# MotherBoard.net
KiCad netlist of a schematic drawn in Altium Designer
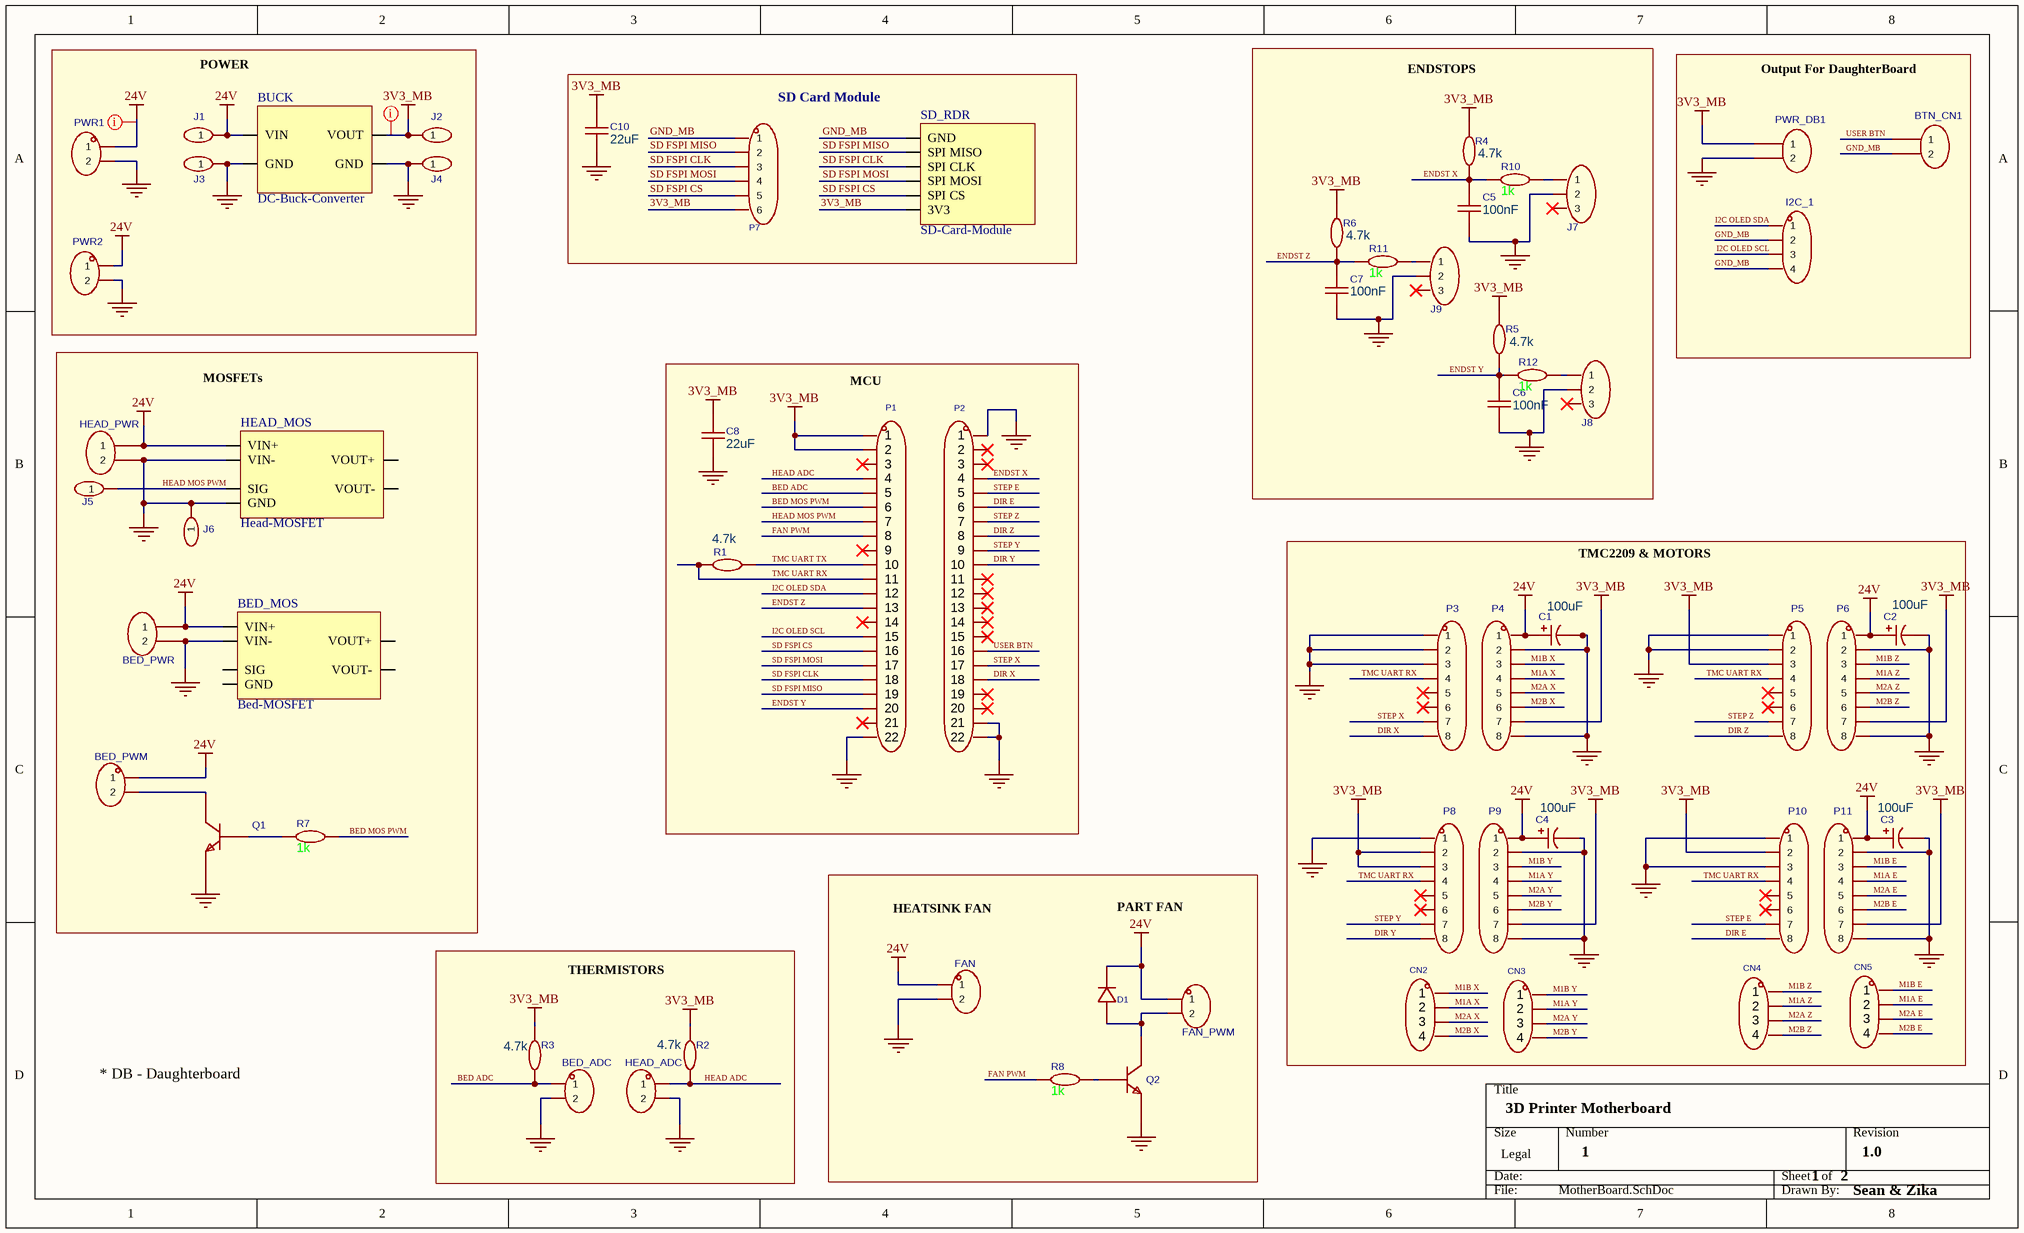
[diagram p0: MotherBoard.SchDoc]

(export (version "E")
  (design (tool "Eeschema 10.0.6"))
  (components
    (comp (ref "BED_ADC")
      (value "sh-xh2.54-2p")
      (footprint "XH-2P")
      (fields (field (name "MANUFACTURER") "深海电子") (field (name "MANUFACTURERPART") "SH-XH2.54-2P"))
      (libsource (lib "FinalProjectSchLib") (part "XH-2P"))
    )
    (comp (ref "BED_MOS")
      (value "Bed-MOSFET")
      (footprint "Bed-MOSFET")
      (libsource (lib "FinalProjectSchLib") (part "Bed-MOSFET"))
    )
    (comp (ref "BED_PWM")
      (value "sh-xh2.54-2p")
      (footprint "XH-2P")
      (fields (field (name "MANUFACTURER") "深海电子") (field (name "MANUFACTURERPART") "SH-XH2.54-2P"))
      (libsource (lib "FinalProjectSchLib") (part "XH-2P"))
    )
    (comp (ref "BED_PWR")
      (value "wj127-5.0-02p-14-00a")
      (footprint "Screw-Terminal-2P")
      (fields
        (field (name "MANUFACTURER") "KANGNEX(康奈克斯电气)")
        (field (name "MANUFACTURERPART") "WJ127-5.0-02P-14-00A")
      )
      (libsource (lib "FinalProjectSchLib") (part "Screw-Terminal-2P"))
    )
    (comp (ref "BTN_CN1")
      (value "wj127-5.0-02p-14-00a")
      (footprint "Screw-Terminal-2P")
      (fields
        (field (name "MANUFACTURER") "KANGNEX(康奈克斯电气)")
        (field (name "MANUFACTURERPART") "WJ127-5.0-02P-14-00A")
      )
      (libsource (lib "FinalProjectSchLib") (part "Screw-Terminal-2P"))
    )
    (comp (ref "BUCK")
      (value "DC-Buck-Converter")
      (footprint "DC-Buck-Converter")
      (libsource (lib "FinalProjectSchLib") (part "DC-Buck-Converter"))
    )
    (comp (ref "C1")
      (value "100uF")
      (footprint "Capacitor-100uF")
      (fields
        (field (name "MANUFACTURER") "DMBJ(振宝佳)")
        (field (name "MANUFACTURERPART") "RVT1H101M0810 100UF 50V")
        (field (name "TOLERANCE") "±20%")
      )
      (libsource (lib "FinalProjectSchLib") (part "Capacitor-100uF"))
    )
    (comp (ref "C2")
      (value "100uF")
      (footprint "Capacitor-100uF")
      (fields
        (field (name "MANUFACTURER") "DMBJ(振宝佳)")
        (field (name "MANUFACTURERPART") "RVT1H101M0810 100UF 50V")
        (field (name "TOLERANCE") "±20%")
      )
      (libsource (lib "FinalProjectSchLib") (part "Capacitor-100uF"))
    )
    (comp (ref "C3")
      (value "100uF")
      (footprint "Capacitor-100uF")
      (fields
        (field (name "MANUFACTURER") "DMBJ(振宝佳)")
        (field (name "MANUFACTURERPART") "RVT1H101M0810 100UF 50V")
        (field (name "TOLERANCE") "±20%")
      )
      (libsource (lib "FinalProjectSchLib") (part "Capacitor-100uF"))
    )
    (comp (ref "C4")
      (value "100uF")
      (footprint "Capacitor-100uF")
      (fields
        (field (name "MANUFACTURER") "DMBJ(振宝佳)")
        (field (name "MANUFACTURERPART") "RVT1H101M0810 100UF 50V")
        (field (name "TOLERANCE") "±20%")
      )
      (libsource (lib "FinalProjectSchLib") (part "Capacitor-100uF"))
    )
    (comp (ref "C5")
      (value "100nF")
      (footprint "Capacitor-100nF-0805")
      (description "Capacitance:100nF Tolerance:±10% Tolerance:±10% Voltage Rating:50V Temperature Coefficient:X7R")
      (fields (field (name "MANUFACTURER") "SAMSUNG(三星)") (field (name "MANUFACTURERPART") "CL21B104KBCNNNC"))
      (libsource (lib "FinalProjectSchLib") (part "Capacitor-100nF-0805"))
    )
    (comp (ref "C6")
      (value "100nF")
      (footprint "Capacitor-100nF-0805")
      (description "Capacitance:100nF Tolerance:±10% Tolerance:±10% Voltage Rating:50V Temperature Coefficient:X7R")
      (fields (field (name "MANUFACTURER") "SAMSUNG(三星)") (field (name "MANUFACTURERPART") "CL21B104KBCNNNC"))
      (libsource (lib "FinalProjectSchLib") (part "Capacitor-100nF-0805"))
    )
    (comp (ref "C7")
      (value "100nF")
      (footprint "Capacitor-100nF-0805")
      (description "Capacitance:100nF Tolerance:±10% Tolerance:±10% Voltage Rating:50V Temperature Coefficient:X7R")
      (fields (field (name "MANUFACTURER") "SAMSUNG(三星)") (field (name "MANUFACTURERPART") "CL21B104KBCNNNC"))
      (libsource (lib "FinalProjectSchLib") (part "Capacitor-100nF-0805"))
    )
    (comp (ref "C8")
      (value "22uF")
      (footprint "Capacitor-22uF-0805")
      (description "Capacitance:22uF Tolerance:±20% Tolerance:±20% Voltage Rating:10V Temperature Coefficient:X5R")
      (fields (field (name "MANUFACTURER") "SAMSUNG(三星)") (field (name "MANUFACTURERPART") "CL21A226MPQNNNE"))
      (libsource (lib "FinalProjectSchLib") (part "Capacitor-22uF-0805"))
    )
    (comp (ref "C10")
      (value "22uF")
      (footprint "Capacitor-22uF-0805")
      (description "Capacitance:22uF Tolerance:±20% Tolerance:±20% Voltage Rating:10V Temperature Coefficient:X5R")
      (fields (field (name "MANUFACTURER") "SAMSUNG(三星)") (field (name "MANUFACTURERPART") "CL21A226MPQNNNE"))
      (libsource (lib "FinalProjectSchLib") (part "Capacitor-22uF-0805"))
    )
    (comp (ref "CN2")
      (value "sh-xh2.54-4p")
      (footprint "XH-4P")
      (fields (field (name "MANUFACTURER") "深海电子") (field (name "MANUFACTURERPART") "SH-XH2.54-4P"))
      (libsource (lib "FinalProjectSchLib") (part "XH-4P"))
    )
    (comp (ref "CN3")
      (value "sh-xh2.54-4p")
      (footprint "XH-4P")
      (fields (field (name "MANUFACTURER") "深海电子") (field (name "MANUFACTURERPART") "SH-XH2.54-4P"))
      (libsource (lib "FinalProjectSchLib") (part "XH-4P"))
    )
    (comp (ref "CN4")
      (value "sh-xh2.54-4p")
      (footprint "XH-4P")
      (fields (field (name "MANUFACTURER") "深海电子") (field (name "MANUFACTURERPART") "SH-XH2.54-4P"))
      (libsource (lib "FinalProjectSchLib") (part "XH-4P"))
    )
    (comp (ref "CN5")
      (value "sh-xh2.54-4p")
      (footprint "XH-4P")
      (fields (field (name "MANUFACTURER") "深海电子") (field (name "MANUFACTURERPART") "SH-XH2.54-4P"))
      (libsource (lib "FinalProjectSchLib") (part "XH-4P"))
    )
    (comp (ref "D1")
      (value "s3mb-13-f")
      (footprint "Diode-1N4007-SMA")
      (fields (field (name "MANUFACTURER") "DIODES(美台)") (field (name "MANUFACTURER PART") "S3MB-13-F"))
      (libsource (lib "FinalProjectSchLib") (part "Diode-1N4007-SMA"))
    )
    (comp (ref "FAN")
      (value "sh-xh2.54-2p")
      (footprint "XH-2P")
      (fields (field (name "MANUFACTURER") "深海电子") (field (name "MANUFACTURERPART") "SH-XH2.54-2P"))
      (libsource (lib "FinalProjectSchLib") (part "XH-2P"))
    )
    (comp (ref "FAN_PWM")
      (value "sh-xh2.54-2p")
      (footprint "XH-2P")
      (fields (field (name "MANUFACTURER") "深海电子") (field (name "MANUFACTURERPART") "SH-XH2.54-2P"))
      (libsource (lib "FinalProjectSchLib") (part "XH-2P"))
    )
    (comp (ref "HEAD_ADC")
      (value "sh-xh2.54-2p")
      (footprint "XH-2P")
      (fields (field (name "MANUFACTURER") "深海电子") (field (name "MANUFACTURERPART") "SH-XH2.54-2P"))
      (libsource (lib "FinalProjectSchLib") (part "XH-2P"))
    )
    (comp (ref "HEAD_MOS")
      (value "Head-MOSFET")
      (footprint "Head-MOSFET")
      (libsource (lib "FinalProjectSchLib") (part "Head-MOSFET"))
    )
    (comp (ref "HEAD_PWR")
      (value "wj127-5.0-02p-14-00a")
      (footprint "Screw-Terminal-2P")
      (fields
        (field (name "MANUFACTURER") "KANGNEX(康奈克斯电气)")
        (field (name "MANUFACTURERPART") "WJ127-5.0-02P-14-00A")
      )
      (libsource (lib "FinalProjectSchLib") (part "Screw-Terminal-2P"))
    )
    (comp (ref "I2C_1")
      (value "wj127-5.0-04p-14-00a")
      (footprint "Screw-Terminal-4P")
      (fields
        (field (name "MANUFACTURER") "KANGNEX(康奈克斯电气)")
        (field (name "MANUFACTURERPART") "WJ127-5.0-04P-14-00A")
      )
      (libsource (lib "FinalProjectSchLib") (part "Screw-Terminal-4P"))
    )
    (comp (ref "J1")
      (value "2.54-1*1p针")
      (footprint "Male-Header-1P")
      (fields (field (name "MANUFACTURER") "BOOMELE(博穆精密)") (field (name "MANUFACTURERPART") "2.54-1*1P针"))
      (libsource (lib "FinalProjectSchLib") (part "Male-Header-1P"))
    )
    (comp (ref "J2")
      (value "2.54-1*1p针")
      (footprint "Male-Header-1P")
      (fields (field (name "MANUFACTURER") "BOOMELE(博穆精密)") (field (name "MANUFACTURERPART") "2.54-1*1P针"))
      (libsource (lib "FinalProjectSchLib") (part "Male-Header-1P"))
    )
    (comp (ref "J3")
      (value "2.54-1*1p针")
      (footprint "Male-Header-1P")
      (fields (field (name "MANUFACTURER") "BOOMELE(博穆精密)") (field (name "MANUFACTURERPART") "2.54-1*1P针"))
      (libsource (lib "FinalProjectSchLib") (part "Male-Header-1P"))
    )
    (comp (ref "J4")
      (value "2.54-1*1p针")
      (footprint "Male-Header-1P")
      (fields (field (name "MANUFACTURER") "BOOMELE(博穆精密)") (field (name "MANUFACTURERPART") "2.54-1*1P针"))
      (libsource (lib "FinalProjectSchLib") (part "Male-Header-1P"))
    )
    (comp (ref "J5")
      (value "2.54-1*1p针")
      (footprint "Male-Header-1P")
      (fields (field (name "MANUFACTURER") "BOOMELE(博穆精密)") (field (name "MANUFACTURERPART") "2.54-1*1P针"))
      (libsource (lib "FinalProjectSchLib") (part "Male-Header-1P"))
    )
    (comp (ref "J6")
      (value "2.54-1*1p针")
      (footprint "Male-Header-1P")
      (fields (field (name "MANUFACTURER") "BOOMELE(博穆精密)") (field (name "MANUFACTURERPART") "2.54-1*1P针"))
      (libsource (lib "FinalProjectSchLib") (part "Male-Header-1P"))
    )
    (comp (ref "J7")
      (value "2.54-1*3p针")
      (footprint "Male-Header-3P")
      (fields (field (name "MANUFACTURER") "BOOMELE(博穆精密)") (field (name "MANUFACTURERPART") "2.54-1*3P针"))
      (libsource (lib "FinalProjectSchLib") (part "Male-Header-3P"))
    )
    (comp (ref "J8")
      (value "2.54-1*3p针")
      (footprint "Male-Header-3P")
      (fields (field (name "MANUFACTURER") "BOOMELE(博穆精密)") (field (name "MANUFACTURERPART") "2.54-1*3P针"))
      (libsource (lib "FinalProjectSchLib") (part "Male-Header-3P"))
    )
    (comp (ref "J9")
      (value "2.54-1*3p针")
      (footprint "Male-Header-3P")
      (fields (field (name "MANUFACTURER") "BOOMELE(博穆精密)") (field (name "MANUFACTURERPART") "2.54-1*3P针"))
      (libsource (lib "FinalProjectSchLib") (part "Male-Header-3P"))
    )
    (comp (ref "P1")
      (value "fh2.54-09-22pzd")
      (footprint "Female-Header-22P")
      (fields (field (name "MANUFACTURER") "XUNPU(讯普)") (field (name "MANUFACTURERPART") "FH2.54-09-22PZD"))
      (libsource (lib "FinalProjectSchLib") (part "Female-Header-22P"))
    )
    (comp (ref "P2")
      (value "fh2.54-09-22pzd")
      (footprint "Female-Header-22P")
      (fields (field (name "MANUFACTURER") "XUNPU(讯普)") (field (name "MANUFACTURERPART") "FH2.54-09-22PZD"))
      (libsource (lib "FinalProjectSchLib") (part "Female-Header-22P"))
    )
    (comp (ref "P3")
      (value "2.54-1*8p母环保")
      (footprint "Female-Header-8P")
      (fields (field (name "MANUFACTURER") "BOOMELE(博穆精密)") (field (name "MANUFACTURERPART") "2.54-1*8P母环保"))
      (libsource (lib "FinalProjectSchLib") (part "Female-Header-8P"))
    )
    (comp (ref "P4")
      (value "2.54-1*8p母环保")
      (footprint "Female-Header-8P")
      (fields (field (name "MANUFACTURER") "BOOMELE(博穆精密)") (field (name "MANUFACTURERPART") "2.54-1*8P母环保"))
      (libsource (lib "FinalProjectSchLib") (part "Female-Header-8P"))
    )
    (comp (ref "P5")
      (value "2.54-1*8p母环保")
      (footprint "Female-Header-8P")
      (fields (field (name "MANUFACTURER") "BOOMELE(博穆精密)") (field (name "MANUFACTURERPART") "2.54-1*8P母环保"))
      (libsource (lib "FinalProjectSchLib") (part "Female-Header-8P"))
    )
    (comp (ref "P6")
      (value "2.54-1*8p母环保")
      (footprint "Female-Header-8P")
      (fields (field (name "MANUFACTURER") "BOOMELE(博穆精密)") (field (name "MANUFACTURERPART") "2.54-1*8P母环保"))
      (libsource (lib "FinalProjectSchLib") (part "Female-Header-8P"))
    )
    (comp (ref "P7")
      (value "2.54-1*6p")
      (footprint "Female-Header-6P")
      (fields (field (name "MANUFACTURER") "BOOMELE(博穆精密)") (field (name "MANUFACTURER PART") "2.54-1*6P母"))
      (libsource (lib "FinalProjectSchLib") (part "Female-Header-6P"))
    )
    (comp (ref "P8")
      (value "2.54-1*8p母环保")
      (footprint "Female-Header-8P")
      (fields (field (name "MANUFACTURER") "BOOMELE(博穆精密)") (field (name "MANUFACTURERPART") "2.54-1*8P母环保"))
      (libsource (lib "FinalProjectSchLib") (part "Female-Header-8P"))
    )
    (comp (ref "P9")
      (value "2.54-1*8p母环保")
      (footprint "Female-Header-8P")
      (fields (field (name "MANUFACTURER") "BOOMELE(博穆精密)") (field (name "MANUFACTURERPART") "2.54-1*8P母环保"))
      (libsource (lib "FinalProjectSchLib") (part "Female-Header-8P"))
    )
    (comp (ref "P10")
      (value "2.54-1*8p母环保")
      (footprint "Female-Header-8P")
      (fields (field (name "MANUFACTURER") "BOOMELE(博穆精密)") (field (name "MANUFACTURERPART") "2.54-1*8P母环保"))
      (libsource (lib "FinalProjectSchLib") (part "Female-Header-8P"))
    )
    (comp (ref "P11")
      (value "2.54-1*8p母环保")
      (footprint "Female-Header-8P")
      (fields (field (name "MANUFACTURER") "BOOMELE(博穆精密)") (field (name "MANUFACTURERPART") "2.54-1*8P母环保"))
      (libsource (lib "FinalProjectSchLib") (part "Female-Header-8P"))
    )
    (comp (ref "PWR1")
      (value "dbt30s-7.62-2p-bk-p")
      (footprint "Barrier-Terminal-2P")
      (fields
        (field (name "MANUFACTURER") "DORABO(地博电气)")
        (field (name "MANUFACTURERPART") "DBT30S-7.62-2P-BK-P")
      )
      (libsource (lib "FinalProjectSchLib") (part "Barrier-Terminal-2P"))
    )
    (comp (ref "PWR2")
      (value "dbt30s-7.62-2p-bk-p")
      (footprint "Barrier-Terminal-2P")
      (fields
        (field (name "MANUFACTURER") "DORABO(地博电气)")
        (field (name "MANUFACTURERPART") "DBT30S-7.62-2P-BK-P")
      )
      (libsource (lib "FinalProjectSchLib") (part "Barrier-Terminal-2P"))
    )
    (comp (ref "PWR_DB1")
      (value "wj127-5.0-02p-14-00a")
      (footprint "Screw-Terminal-2P")
      (fields
        (field (name "MANUFACTURER") "KANGNEX(康奈克斯电气)")
        (field (name "MANUFACTURERPART") "WJ127-5.0-02P-14-00A")
      )
      (libsource (lib "FinalProjectSchLib") (part "Screw-Terminal-2P"))
    )
    (comp (ref "Q1")
      (value "ktc3265(range:160-320)")
      (footprint "NPN-SOT23-30V")
      (fields
        (field (name "MANUFACTURER") "CJ(江苏长电/长晶)")
        (field (name "MANUFACTURERPART") "KTC3265(RANGE:160-320)")
      )
      (libsource (lib "FinalProjectSchLib") (part "NPN-SOT23-30V"))
    )
    (comp (ref "Q2")
      (value "ktc3265(range:160-320)")
      (footprint "NPN-SOT23-30V")
      (fields
        (field (name "MANUFACTURER") "CJ(江苏长电/长晶)")
        (field (name "MANUFACTURERPART") "KTC3265(RANGE:160-320)")
      )
      (libsource (lib "FinalProjectSchLib") (part "NPN-SOT23-30V"))
    )
    (comp (ref "R1")
      (value "4.7k")
      (footprint "Resistor-4.7k-0805")
      (fields
        (field (name "MANUFACTURER") "UNI-ROYAL(厚声)")
        (field (name "MANUFACTURERPART") "0805W8F4701T5E")
        (field (name "TOLERANCE") "±1%")
      )
      (libsource (lib "FinalProjectSchLib") (part "Resistor-4.7k-0805"))
    )
    (comp (ref "R2")
      (value "4.7k")
      (footprint "Resistor-4.7k-0805")
      (fields
        (field (name "MANUFACTURER") "UNI-ROYAL(厚声)")
        (field (name "MANUFACTURERPART") "0805W8F4701T5E")
        (field (name "TOLERANCE") "±1%")
      )
      (libsource (lib "FinalProjectSchLib") (part "Resistor-4.7k-0805"))
    )
    (comp (ref "R3")
      (value "4.7k")
      (footprint "Resistor-4.7k-0805")
      (fields
        (field (name "MANUFACTURER") "UNI-ROYAL(厚声)")
        (field (name "MANUFACTURERPART") "0805W8F4701T5E")
        (field (name "TOLERANCE") "±1%")
      )
      (libsource (lib "FinalProjectSchLib") (part "Resistor-4.7k-0805"))
    )
    (comp (ref "R4")
      (value "4.7k")
      (footprint "Resistor-4.7k-0805")
      (fields
        (field (name "MANUFACTURER") "UNI-ROYAL(厚声)")
        (field (name "MANUFACTURERPART") "0805W8F4701T5E")
        (field (name "TOLERANCE") "±1%")
      )
      (libsource (lib "FinalProjectSchLib") (part "Resistor-4.7k-0805"))
    )
    (comp (ref "R5")
      (value "4.7k")
      (footprint "Resistor-4.7k-0805")
      (fields
        (field (name "MANUFACTURER") "UNI-ROYAL(厚声)")
        (field (name "MANUFACTURERPART") "0805W8F4701T5E")
        (field (name "TOLERANCE") "±1%")
      )
      (libsource (lib "FinalProjectSchLib") (part "Resistor-4.7k-0805"))
    )
    (comp (ref "R6")
      (value "4.7k")
      (footprint "Resistor-4.7k-0805")
      (fields
        (field (name "MANUFACTURER") "UNI-ROYAL(厚声)")
        (field (name "MANUFACTURERPART") "0805W8F4701T5E")
        (field (name "TOLERANCE") "±1%")
      )
      (libsource (lib "FinalProjectSchLib") (part "Resistor-4.7k-0805"))
    )
    (comp (ref "R7")
      (value "1k")
      (footprint "Resistor-1k-0805")
      (fields
        (field (name "MANUFACTURER") "UNI-ROYAL(厚声)")
        (field (name "MANUFACTURERPART") "0805W8F1001T5E")
        (field (name "TOLERANCE") "±1%")
      )
      (libsource (lib "FinalProjectSchLib") (part "Resistor-1k-0805"))
    )
    (comp (ref "R8")
      (value "1k")
      (footprint "Resistor-1k-0805")
      (fields
        (field (name "MANUFACTURER") "UNI-ROYAL(厚声)")
        (field (name "MANUFACTURERPART") "0805W8F1001T5E")
        (field (name "TOLERANCE") "±1%")
      )
      (libsource (lib "FinalProjectSchLib") (part "Resistor-1k-0805"))
    )
    (comp (ref "R10")
      (value "1k")
      (footprint "Resistor-1k-0805")
      (fields
        (field (name "MANUFACTURER") "UNI-ROYAL(厚声)")
        (field (name "MANUFACTURERPART") "0805W8F1001T5E")
        (field (name "TOLERANCE") "±1%")
      )
      (libsource (lib "FinalProjectSchLib") (part "Resistor-1k-0805"))
    )
    (comp (ref "R11")
      (value "1k")
      (footprint "Resistor-1k-0805")
      (fields
        (field (name "MANUFACTURER") "UNI-ROYAL(厚声)")
        (field (name "MANUFACTURERPART") "0805W8F1001T5E")
        (field (name "TOLERANCE") "±1%")
      )
      (libsource (lib "FinalProjectSchLib") (part "Resistor-1k-0805"))
    )
    (comp (ref "R12")
      (value "1k")
      (footprint "Resistor-1k-0805")
      (fields
        (field (name "MANUFACTURER") "UNI-ROYAL(厚声)")
        (field (name "MANUFACTURERPART") "0805W8F1001T5E")
        (field (name "TOLERANCE") "±1%")
      )
      (libsource (lib "FinalProjectSchLib") (part "Resistor-1k-0805"))
    )
    (comp (ref "SD_RDR")
      (value "SD-Card-Module")
      (footprint "SD-Card-Module")
      (libsource (lib "FinalProjectSchLib") (part "SD-Card-Module"))
    )
  )
  (nets
    (net (code "1") (name "/BED ADC") (class "Default")
      (node (ref "BED_ADC") (pin "1") (pinfunction "1_1") (pintype "passive"))
      (node (ref "P1") (pin "5") (pinfunction "5_5") (pintype "passive"))
      (node (ref "R3") (pin "1") (pinfunction "1_1") (pintype "passive"))
    )
    (net (code "2") (name "/BED MOS PWM") (class "Default")
      (node (ref "P1") (pin "6") (pinfunction "6_6") (pintype "passive"))
      (node (ref "R7") (pin "2") (pinfunction "2_2") (pintype "passive"))
    )
    (net (code "3") (name "/DIR E") (class "Default")
      (node (ref "P10") (pin "8") (pinfunction "8_8") (pintype "passive"))
      (node (ref "P2") (pin "6") (pinfunction "6_6") (pintype "passive"))
    )
    (net (code "4") (name "/DIR X") (class "Default")
      (node (ref "P2") (pin "18") (pinfunction "18_18") (pintype "passive"))
      (node (ref "P3") (pin "8") (pinfunction "8_8") (pintype "passive"))
    )
    (net (code "5") (name "/DIR Y") (class "Default")
      (node (ref "P2") (pin "10") (pinfunction "10_10") (pintype "passive"))
      (node (ref "P8") (pin "8") (pinfunction "8_8") (pintype "passive"))
    )
    (net (code "6") (name "/DIR Z") (class "Default")
      (node (ref "P2") (pin "8") (pinfunction "8_8") (pintype "passive"))
      (node (ref "P5") (pin "8") (pinfunction "8_8") (pintype "passive"))
    )
    (net (code "7") (name "/ENDST X") (class "Default")
      (node (ref "C5") (pin "2") (pinfunction "2_2") (pintype "passive"))
      (node (ref "P2") (pin "4") (pinfunction "4_4") (pintype "passive"))
      (node (ref "R10") (pin "1") (pinfunction "1_1") (pintype "passive"))
      (node (ref "R4") (pin "1") (pinfunction "1_1") (pintype "passive"))
    )
    (net (code "8") (name "/ENDST Y") (class "Default")
      (node (ref "C6") (pin "2") (pinfunction "2_2") (pintype "passive"))
      (node (ref "P1") (pin "20") (pinfunction "20_20") (pintype "passive"))
      (node (ref "R12") (pin "1") (pinfunction "1_1") (pintype "passive"))
      (node (ref "R5") (pin "1") (pinfunction "1_1") (pintype "passive"))
    )
    (net (code "9") (name "/ENDST Z") (class "Default")
      (node (ref "C7") (pin "2") (pinfunction "2_2") (pintype "passive"))
      (node (ref "P1") (pin "13") (pinfunction "13_13") (pintype "passive"))
      (node (ref "R11") (pin "1") (pinfunction "1_1") (pintype "passive"))
      (node (ref "R6") (pin "1") (pinfunction "1_1") (pintype "passive"))
    )
    (net (code "10") (name "/FAN PWM") (class "Default")
      (node (ref "P1") (pin "8") (pinfunction "8_8") (pintype "passive"))
      (node (ref "R8") (pin "1") (pinfunction "1_1") (pintype "passive"))
    )
    (net (code "11") (name "/HEAD ADC") (class "Default")
      (node (ref "HEAD_ADC") (pin "1") (pinfunction "1_1") (pintype "passive"))
      (node (ref "P1") (pin "4") (pinfunction "4_4") (pintype "passive"))
      (node (ref "R2") (pin "2") (pinfunction "2_2") (pintype "passive"))
    )
    (net (code "12") (name "/HEAD MOS PWM") (class "Default")
      (node (ref "HEAD_MOS") (pin "3") (pinfunction "SIG_3") (pintype "passive"))
      (node (ref "J5") (pin "1") (pinfunction "1_1") (pintype "passive"))
      (node (ref "P1") (pin "7") (pinfunction "7_7") (pintype "passive"))
    )
    (net (code "13") (name "/I2C OLED SCL") (class "Default")
      (node (ref "I2C_1") (pin "3") (pinfunction "3_3") (pintype "passive"))
      (node (ref "P1") (pin "15") (pinfunction "15_15") (pintype "passive"))
    )
    (net (code "14") (name "/I2C OLED SDA") (class "Default")
      (node (ref "I2C_1") (pin "1") (pinfunction "1_1") (pintype "passive"))
      (node (ref "P1") (pin "12") (pinfunction "12_12") (pintype "passive"))
    )
    (net (code "15") (name "/M1A E") (class "Default")
      (node (ref "CN5") (pin "2") (pinfunction "2_2") (pintype "passive"))
      (node (ref "P11") (pin "4") (pinfunction "4_4") (pintype "passive"))
    )
    (net (code "16") (name "/M1A X") (class "Default")
      (node (ref "CN2") (pin "2") (pinfunction "2_2") (pintype "passive"))
      (node (ref "P4") (pin "4") (pinfunction "4_4") (pintype "passive"))
    )
    (net (code "17") (name "/M1A Y") (class "Default")
      (node (ref "CN3") (pin "2") (pinfunction "2_2") (pintype "passive"))
      (node (ref "P9") (pin "4") (pinfunction "4_4") (pintype "passive"))
    )
    (net (code "18") (name "/M1A Z") (class "Default")
      (node (ref "CN4") (pin "2") (pinfunction "2_2") (pintype "passive"))
      (node (ref "P6") (pin "4") (pinfunction "4_4") (pintype "passive"))
    )
    (net (code "19") (name "/M1B E") (class "Default")
      (node (ref "CN5") (pin "1") (pinfunction "1_1") (pintype "passive"))
      (node (ref "P11") (pin "3") (pinfunction "3_3") (pintype "passive"))
    )
    (net (code "20") (name "/M1B X") (class "Default")
      (node (ref "CN2") (pin "1") (pinfunction "1_1") (pintype "passive"))
      (node (ref "P4") (pin "3") (pinfunction "3_3") (pintype "passive"))
    )
    (net (code "21") (name "/M1B Y") (class "Default")
      (node (ref "CN3") (pin "1") (pinfunction "1_1") (pintype "passive"))
      (node (ref "P9") (pin "3") (pinfunction "3_3") (pintype "passive"))
    )
    (net (code "22") (name "/M1B Z") (class "Default")
      (node (ref "CN4") (pin "1") (pinfunction "1_1") (pintype "passive"))
      (node (ref "P6") (pin "3") (pinfunction "3_3") (pintype "passive"))
    )
    (net (code "23") (name "/M2A E") (class "Default")
      (node (ref "CN5") (pin "3") (pinfunction "3_3") (pintype "passive"))
      (node (ref "P11") (pin "5") (pinfunction "5_5") (pintype "passive"))
    )
    (net (code "24") (name "/M2A X") (class "Default")
      (node (ref "CN2") (pin "3") (pinfunction "3_3") (pintype "passive"))
      (node (ref "P4") (pin "5") (pinfunction "5_5") (pintype "passive"))
    )
    (net (code "25") (name "/M2A Y") (class "Default")
      (node (ref "CN3") (pin "3") (pinfunction "3_3") (pintype "passive"))
      (node (ref "P9") (pin "5") (pinfunction "5_5") (pintype "passive"))
    )
    (net (code "26") (name "/M2A Z") (class "Default")
      (node (ref "CN4") (pin "3") (pinfunction "3_3") (pintype "passive"))
      (node (ref "P6") (pin "5") (pinfunction "5_5") (pintype "passive"))
    )
    (net (code "27") (name "/M2B E") (class "Default")
      (node (ref "CN5") (pin "4") (pinfunction "4_4") (pintype "passive"))
      (node (ref "P11") (pin "6") (pinfunction "6_6") (pintype "passive"))
    )
    (net (code "28") (name "/M2B X") (class "Default")
      (node (ref "CN2") (pin "4") (pinfunction "4_4") (pintype "passive"))
      (node (ref "P4") (pin "6") (pinfunction "6_6") (pintype "passive"))
    )
    (net (code "29") (name "/M2B Y") (class "Default")
      (node (ref "CN3") (pin "4") (pinfunction "4_4") (pintype "passive"))
      (node (ref "P9") (pin "6") (pinfunction "6_6") (pintype "passive"))
    )
    (net (code "30") (name "/M2B Z") (class "Default")
      (node (ref "CN4") (pin "4") (pinfunction "4_4") (pintype "passive"))
      (node (ref "P6") (pin "6") (pinfunction "6_6") (pintype "passive"))
    )
    (net (code "31") (name "/SD FSPI CLK") (class "Default")
      (node (ref "P1") (pin "18") (pinfunction "18_18") (pintype "passive"))
      (node (ref "P7") (pin "3") (pinfunction "3_3") (pintype "passive"))
      (node (ref "SD_RDR") (pin "3") (pinfunction "SPI_CLK_3") (pintype "passive"))
    )
    (net (code "32") (name "/SD FSPI CS") (class "Default")
      (node (ref "P1") (pin "16") (pinfunction "16_16") (pintype "passive"))
      (node (ref "P7") (pin "5") (pinfunction "5_5") (pintype "passive"))
      (node (ref "SD_RDR") (pin "5") (pinfunction "SPI_CS_5") (pintype "passive"))
    )
    (net (code "33") (name "/SD FSPI MISO") (class "Default")
      (node (ref "P1") (pin "19") (pinfunction "19_19") (pintype "passive"))
      (node (ref "P7") (pin "2") (pinfunction "2_2") (pintype "passive"))
      (node (ref "SD_RDR") (pin "2") (pinfunction "SPI_MISO_2") (pintype "passive"))
    )
    (net (code "34") (name "/SD FSPI MOSI") (class "Default")
      (node (ref "P1") (pin "17") (pinfunction "17_17") (pintype "passive"))
      (node (ref "P7") (pin "4") (pinfunction "4_4") (pintype "passive"))
      (node (ref "SD_RDR") (pin "4") (pinfunction "SPI_MOSI_4") (pintype "passive"))
    )
    (net (code "35") (name "/STEP E") (class "Default")
      (node (ref "P10") (pin "7") (pinfunction "7_7") (pintype "passive"))
      (node (ref "P2") (pin "5") (pinfunction "5_5") (pintype "passive"))
    )
    (net (code "36") (name "/STEP X") (class "Default")
      (node (ref "P2") (pin "17") (pinfunction "17_17") (pintype "passive"))
      (node (ref "P3") (pin "7") (pinfunction "7_7") (pintype "passive"))
    )
    (net (code "37") (name "/STEP Y") (class "Default")
      (node (ref "P2") (pin "9") (pinfunction "9_9") (pintype "passive"))
      (node (ref "P8") (pin "7") (pinfunction "7_7") (pintype "passive"))
    )
    (net (code "38") (name "/STEP Z") (class "Default")
      (node (ref "P2") (pin "7") (pinfunction "7_7") (pintype "passive"))
      (node (ref "P5") (pin "7") (pinfunction "7_7") (pintype "passive"))
    )
    (net (code "39") (name "/TMC UART RX") (class "Default")
      (node (ref "P1") (pin "11") (pinfunction "11_11") (pintype "passive"))
      (node (ref "P10") (pin "4") (pinfunction "4_4") (pintype "passive"))
      (node (ref "P3") (pin "4") (pinfunction "4_4") (pintype "passive"))
      (node (ref "P5") (pin "4") (pinfunction "4_4") (pintype "passive"))
      (node (ref "P8") (pin "4") (pinfunction "4_4") (pintype "passive"))
      (node (ref "R1") (pin "2") (pinfunction "2_2") (pintype "passive"))
    )
    (net (code "40") (name "/TMC UART TX") (class "Default")
      (node (ref "P1") (pin "10") (pinfunction "10_10") (pintype "passive"))
      (node (ref "R1") (pin "1") (pinfunction "1_1") (pintype "passive"))
    )
    (net (code "41") (name "/USER BTN") (class "Default")
      (node (ref "BTN_CN1") (pin "1") (pinfunction "1_1") (pintype "passive"))
      (node (ref "P2") (pin "16") (pinfunction "16_16") (pintype "passive"))
    )
    (net (code "42") (name "3V3_MB") (class "Default")
      (node (ref "BUCK") (pin "3") (pinfunction "VOUT_3") (pintype "passive"))
      (node (ref "C10") (pin "1") (pinfunction "1_1") (pintype "passive"))
      (node (ref "C8") (pin "2") (pinfunction "2_2") (pintype "passive"))
      (node (ref "J2") (pin "1") (pinfunction "1_1") (pintype "passive"))
      (node (ref "P1") (pin "1") (pinfunction "1_1") (pintype "passive"))
      (node (ref "P1") (pin "2") (pinfunction "2_2") (pintype "passive"))
      (node (ref "P10") (pin "2") (pinfunction "2_2") (pintype "passive"))
      (node (ref "P11") (pin "7") (pinfunction "7_7") (pintype "passive"))
      (node (ref "P4") (pin "7") (pinfunction "7_7") (pintype "passive"))
      (node (ref "P5") (pin "3") (pinfunction "3_3") (pintype "passive"))
      (node (ref "P6") (pin "7") (pinfunction "7_7") (pintype "passive"))
      (node (ref "P7") (pin "6") (pinfunction "6_6") (pintype "passive"))
      (node (ref "P8") (pin "2") (pinfunction "2_2") (pintype "passive"))
      (node (ref "P8") (pin "3") (pinfunction "3_3") (pintype "passive"))
      (node (ref "P9") (pin "7") (pinfunction "7_7") (pintype "passive"))
      (node (ref "PWR_DB1") (pin "1") (pinfunction "1_1") (pintype "passive"))
      (node (ref "R2") (pin "1") (pinfunction "1_1") (pintype "passive"))
      (node (ref "R3") (pin "2") (pinfunction "2_2") (pintype "passive"))
      (node (ref "R4") (pin "2") (pinfunction "2_2") (pintype "passive"))
      (node (ref "R5") (pin "2") (pinfunction "2_2") (pintype "passive"))
      (node (ref "R6") (pin "2") (pinfunction "2_2") (pintype "passive"))
      (node (ref "SD_RDR") (pin "6") (pinfunction "3V3_6") (pintype "passive"))
    )
    (net (code "43") (name "24V") (class "Default")
      (node (ref "BED_MOS") (pin "1") (pinfunction "VIN+_1") (pintype "passive"))
      (node (ref "BED_PWM") (pin "1") (pinfunction "1_1") (pintype "passive"))
      (node (ref "BED_PWR") (pin "1") (pinfunction "1_1") (pintype "passive"))
      (node (ref "BUCK") (pin "1") (pinfunction "VIN_1") (pintype "passive"))
      (node (ref "C1") (pin "1") (pinfunction "1_1") (pintype "passive"))
      (node (ref "C2") (pin "1") (pinfunction "1_1") (pintype "passive"))
      (node (ref "C3") (pin "1") (pinfunction "1_1") (pintype "passive"))
      (node (ref "C4") (pin "1") (pinfunction "1_1") (pintype "passive"))
      (node (ref "D1") (pin "1") (pinfunction "1_1") (pintype "passive"))
      (node (ref "FAN") (pin "1") (pinfunction "1_1") (pintype "passive"))
      (node (ref "FAN_PWM") (pin "1") (pinfunction "1_1") (pintype "passive"))
      (node (ref "HEAD_MOS") (pin "1") (pinfunction "VIN+_1") (pintype "passive"))
      (node (ref "HEAD_PWR") (pin "1") (pinfunction "1_1") (pintype "passive"))
      (node (ref "J1") (pin "1") (pinfunction "1_1") (pintype "passive"))
      (node (ref "P11") (pin "1") (pinfunction "1_1") (pintype "passive"))
      (node (ref "P4") (pin "1") (pinfunction "1_1") (pintype "passive"))
      (node (ref "P6") (pin "1") (pinfunction "1_1") (pintype "passive"))
      (node (ref "P9") (pin "1") (pinfunction "1_1") (pintype "passive"))
      (node (ref "PWR1") (pin "1") (pinfunction "1_1") (pintype "passive"))
      (node (ref "PWR2") (pin "1") (pinfunction "1_1") (pintype "passive"))
    )
    (net (code "44") (name "GND_MB") (class "Default")
      (node (ref "BED_ADC") (pin "2") (pinfunction "2_2") (pintype "passive"))
      (node (ref "BED_MOS") (pin "2") (pinfunction "VIN-_2") (pintype "passive"))
      (node (ref "BED_PWR") (pin "2") (pinfunction "2_2") (pintype "passive"))
      (node (ref "BTN_CN1") (pin "2") (pinfunction "2_2") (pintype "passive"))
      (node (ref "BUCK") (pin "2") (pinfunction "GND_2") (pintype "passive"))
      (node (ref "BUCK") (pin "4") (pinfunction "GND_4") (pintype "passive"))
      (node (ref "C1") (pin "2") (pinfunction "2_2") (pintype "passive"))
      (node (ref "C10") (pin "2") (pinfunction "2_2") (pintype "passive"))
      (node (ref "C2") (pin "2") (pinfunction "2_2") (pintype "passive"))
      (node (ref "C3") (pin "2") (pinfunction "2_2") (pintype "passive"))
      (node (ref "C4") (pin "2") (pinfunction "2_2") (pintype "passive"))
      (node (ref "C5") (pin "1") (pinfunction "1_1") (pintype "passive"))
      (node (ref "C6") (pin "1") (pinfunction "1_1") (pintype "passive"))
      (node (ref "C7") (pin "1") (pinfunction "1_1") (pintype "passive"))
      (node (ref "C8") (pin "1") (pinfunction "1_1") (pintype "passive"))
      (node (ref "FAN") (pin "2") (pinfunction "2_2") (pintype "passive"))
      (node (ref "HEAD_ADC") (pin "2") (pinfunction "2_2") (pintype "passive"))
      (node (ref "HEAD_MOS") (pin "2") (pinfunction "VIN-_2") (pintype "passive"))
      (node (ref "HEAD_MOS") (pin "4") (pinfunction "GND_4") (pintype "passive"))
      (node (ref "HEAD_PWR") (pin "2") (pinfunction "2_2") (pintype "passive"))
      (node (ref "I2C_1") (pin "2") (pinfunction "2_2") (pintype "passive"))
      (node (ref "I2C_1") (pin "4") (pinfunction "4_4") (pintype "passive"))
      (node (ref "J3") (pin "1") (pinfunction "1_1") (pintype "passive"))
      (node (ref "J4") (pin "1") (pinfunction "1_1") (pintype "passive"))
      (node (ref "J6") (pin "1") (pinfunction "1_1") (pintype "passive"))
      (node (ref "J7") (pin "2") (pinfunction "2_2") (pintype "passive"))
      (node (ref "J8") (pin "2") (pinfunction "2_2") (pintype "passive"))
      (node (ref "J9") (pin "2") (pinfunction "2_2") (pintype "passive"))
      (node (ref "P1") (pin "22") (pinfunction "22_22") (pintype "passive"))
      (node (ref "P10") (pin "1") (pinfunction "1_1") (pintype "passive"))
      (node (ref "P10") (pin "3") (pinfunction "3_3") (pintype "passive"))
      (node (ref "P11") (pin "2") (pinfunction "2_2") (pintype "passive"))
      (node (ref "P11") (pin "8") (pinfunction "8_8") (pintype "passive"))
      (node (ref "P2") (pin "1") (pinfunction "1_1") (pintype "passive"))
      (node (ref "P2") (pin "21") (pinfunction "21_21") (pintype "passive"))
      (node (ref "P2") (pin "22") (pinfunction "22_22") (pintype "passive"))
      (node (ref "P3") (pin "1") (pinfunction "1_1") (pintype "passive"))
      (node (ref "P3") (pin "2") (pinfunction "2_2") (pintype "passive"))
      (node (ref "P3") (pin "3") (pinfunction "3_3") (pintype "passive"))
      (node (ref "P4") (pin "2") (pinfunction "2_2") (pintype "passive"))
      (node (ref "P4") (pin "8") (pinfunction "8_8") (pintype "passive"))
      (node (ref "P5") (pin "1") (pinfunction "1_1") (pintype "passive"))
      (node (ref "P5") (pin "2") (pinfunction "2_2") (pintype "passive"))
      (node (ref "P6") (pin "2") (pinfunction "2_2") (pintype "passive"))
      (node (ref "P6") (pin "8") (pinfunction "8_8") (pintype "passive"))
      (node (ref "P7") (pin "1") (pinfunction "1_1") (pintype "passive"))
      (node (ref "P8") (pin "1") (pinfunction "1_1") (pintype "passive"))
      (node (ref "P9") (pin "2") (pinfunction "2_2") (pintype "passive"))
      (node (ref "P9") (pin "8") (pinfunction "8_8") (pintype "passive"))
      (node (ref "PWR1") (pin "2") (pinfunction "2_2") (pintype "passive"))
      (node (ref "PWR2") (pin "2") (pinfunction "2_2") (pintype "passive"))
      (node (ref "PWR_DB1") (pin "2") (pinfunction "2_2") (pintype "passive"))
      (node (ref "Q1") (pin "2") (pinfunction "E_2") (pintype "passive"))
      (node (ref "Q2") (pin "2") (pinfunction "E_2") (pintype "passive"))
      (node (ref "SD_RDR") (pin "1") (pinfunction "GND_1") (pintype "passive"))
    )
    (net (code "45") (name "Net-(J7-Pad1)") (class "Default")
      (node (ref "J7") (pin "1") (pinfunction "1_1") (pintype "passive"))
      (node (ref "R10") (pin "2") (pinfunction "2_2") (pintype "passive"))
    )
    (net (code "46") (name "Net-(J8-Pad1)") (class "Default")
      (node (ref "J8") (pin "1") (pinfunction "1_1") (pintype "passive"))
      (node (ref "R12") (pin "2") (pinfunction "2_2") (pintype "passive"))
    )
    (net (code "47") (name "Net-(J9-Pad1)") (class "Default")
      (node (ref "J9") (pin "1") (pinfunction "1_1") (pintype "passive"))
      (node (ref "R11") (pin "2") (pinfunction "2_2") (pintype "passive"))
    )
    (net (code "48") (name "Net-(Q1-B)") (class "Default")
      (node (ref "Q1") (pin "1") (pinfunction "B_1") (pintype "passive"))
      (node (ref "R7") (pin "1") (pinfunction "1_1") (pintype "passive"))
    )
    (net (code "49") (name "Net-(Q1-C)") (class "Default")
      (node (ref "BED_PWM") (pin "2") (pinfunction "2_2") (pintype "passive"))
      (node (ref "Q1") (pin "3") (pinfunction "C_3") (pintype "passive"))
    )
    (net (code "50") (name "Net-(Q2-B)") (class "Default")
      (node (ref "Q2") (pin "1") (pinfunction "B_1") (pintype "passive"))
      (node (ref "R8") (pin "2") (pinfunction "2_2") (pintype "passive"))
    )
    (net (code "51") (name "Net-(Q2-C)") (class "Default")
      (node (ref "D1") (pin "2") (pinfunction "2_2") (pintype "passive"))
      (node (ref "FAN_PWM") (pin "2") (pinfunction "2_2") (pintype "passive"))
      (node (ref "Q2") (pin "3") (pinfunction "C_3") (pintype "passive"))
    )
    (net (code "52") (name "unconnected-(BED_MOS-GND-Pad4)") (class "Default")
      (node (ref "BED_MOS") (pin "4") (pinfunction "GND_4") (pintype "passive"))
    )
    (net (code "53") (name "unconnected-(BED_MOS-SIG-Pad3)") (class "Default")
      (node (ref "BED_MOS") (pin "3") (pinfunction "SIG_3") (pintype "passive"))
    )
    (net (code "54") (name "unconnected-(BED_MOS-VOUT+-Pad5)") (class "Default")
      (node (ref "BED_MOS") (pin "5") (pinfunction "VOUT+_5") (pintype "passive"))
    )
    (net (code "55") (name "unconnected-(BED_MOS-VOUT--Pad6)") (class "Default")
      (node (ref "BED_MOS") (pin "6") (pinfunction "VOUT-_6") (pintype "passive"))
    )
    (net (code "56") (name "unconnected-(HEAD_MOS-VOUT+-Pad5)") (class "Default")
      (node (ref "HEAD_MOS") (pin "5") (pinfunction "VOUT+_5") (pintype "passive"))
    )
    (net (code "57") (name "unconnected-(HEAD_MOS-VOUT--Pad6)") (class "Default")
      (node (ref "HEAD_MOS") (pin "6") (pinfunction "VOUT-_6") (pintype "passive"))
    )
    (net (code "58") (name "unconnected-(J7-Pad3)") (class "Default")
      (node (ref "J7") (pin "3") (pinfunction "3_3") (pintype "passive+no_connect"))
    )
    (net (code "59") (name "unconnected-(J8-Pad3)") (class "Default")
      (node (ref "J8") (pin "3") (pinfunction "3_3") (pintype "passive+no_connect"))
    )
    (net (code "60") (name "unconnected-(J9-Pad3)") (class "Default")
      (node (ref "J9") (pin "3") (pinfunction "3_3") (pintype "passive+no_connect"))
    )
    (net (code "61") (name "unconnected-(P1-Pad3)") (class "Default")
      (node (ref "P1") (pin "3") (pinfunction "3_3") (pintype "passive+no_connect"))
    )
    (net (code "62") (name "unconnected-(P1-Pad9)") (class "Default")
      (node (ref "P1") (pin "9") (pinfunction "9_9") (pintype "passive+no_connect"))
    )
    (net (code "63") (name "unconnected-(P1-Pad14)") (class "Default")
      (node (ref "P1") (pin "14") (pinfunction "14_14") (pintype "passive+no_connect"))
    )
    (net (code "64") (name "unconnected-(P1-Pad21)") (class "Default")
      (node (ref "P1") (pin "21") (pinfunction "21_21") (pintype "passive+no_connect"))
    )
    (net (code "65") (name "unconnected-(P2-Pad2)") (class "Default")
      (node (ref "P2") (pin "2") (pinfunction "2_2") (pintype "passive+no_connect"))
    )
    (net (code "66") (name "unconnected-(P2-Pad3)") (class "Default")
      (node (ref "P2") (pin "3") (pinfunction "3_3") (pintype "passive+no_connect"))
    )
    (net (code "67") (name "unconnected-(P2-Pad11)") (class "Default")
      (node (ref "P2") (pin "11") (pinfunction "11_11") (pintype "passive+no_connect"))
    )
    (net (code "68") (name "unconnected-(P2-Pad12)") (class "Default")
      (node (ref "P2") (pin "12") (pinfunction "12_12") (pintype "passive+no_connect"))
    )
    (net (code "69") (name "unconnected-(P2-Pad13)") (class "Default")
      (node (ref "P2") (pin "13") (pinfunction "13_13") (pintype "passive+no_connect"))
    )
    (net (code "70") (name "unconnected-(P2-Pad14)") (class "Default")
      (node (ref "P2") (pin "14") (pinfunction "14_14") (pintype "passive+no_connect"))
    )
    (net (code "71") (name "unconnected-(P2-Pad15)") (class "Default")
      (node (ref "P2") (pin "15") (pinfunction "15_15") (pintype "passive+no_connect"))
    )
    (net (code "72") (name "unconnected-(P2-Pad19)") (class "Default")
      (node (ref "P2") (pin "19") (pinfunction "19_19") (pintype "passive+no_connect"))
    )
    (net (code "73") (name "unconnected-(P2-Pad20)") (class "Default")
      (node (ref "P2") (pin "20") (pinfunction "20_20") (pintype "passive+no_connect"))
    )
    (net (code "74") (name "unconnected-(P3-Pad5)") (class "Default")
      (node (ref "P3") (pin "5") (pinfunction "5_5") (pintype "passive+no_connect"))
    )
    (net (code "75") (name "unconnected-(P3-Pad6)") (class "Default")
      (node (ref "P3") (pin "6") (pinfunction "6_6") (pintype "passive+no_connect"))
    )
    (net (code "76") (name "unconnected-(P5-Pad5)") (class "Default")
      (node (ref "P5") (pin "5") (pinfunction "5_5") (pintype "passive+no_connect"))
    )
    (net (code "77") (name "unconnected-(P5-Pad6)") (class "Default")
      (node (ref "P5") (pin "6") (pinfunction "6_6") (pintype "passive+no_connect"))
    )
    (net (code "78") (name "unconnected-(P8-Pad5)") (class "Default")
      (node (ref "P8") (pin "5") (pinfunction "5_5") (pintype "passive+no_connect"))
    )
    (net (code "79") (name "unconnected-(P8-Pad6)") (class "Default")
      (node (ref "P8") (pin "6") (pinfunction "6_6") (pintype "passive+no_connect"))
    )
    (net (code "80") (name "unconnected-(P10-Pad5)") (class "Default")
      (node (ref "P10") (pin "5") (pinfunction "5_5") (pintype "passive+no_connect"))
    )
    (net (code "81") (name "unconnected-(P10-Pad6)") (class "Default")
      (node (ref "P10") (pin "6") (pinfunction "6_6") (pintype "passive+no_connect"))
    )
  )
)
